# Motor_Driver_MK1.net
KiCad netlist of a schematic drawn in EAGLE
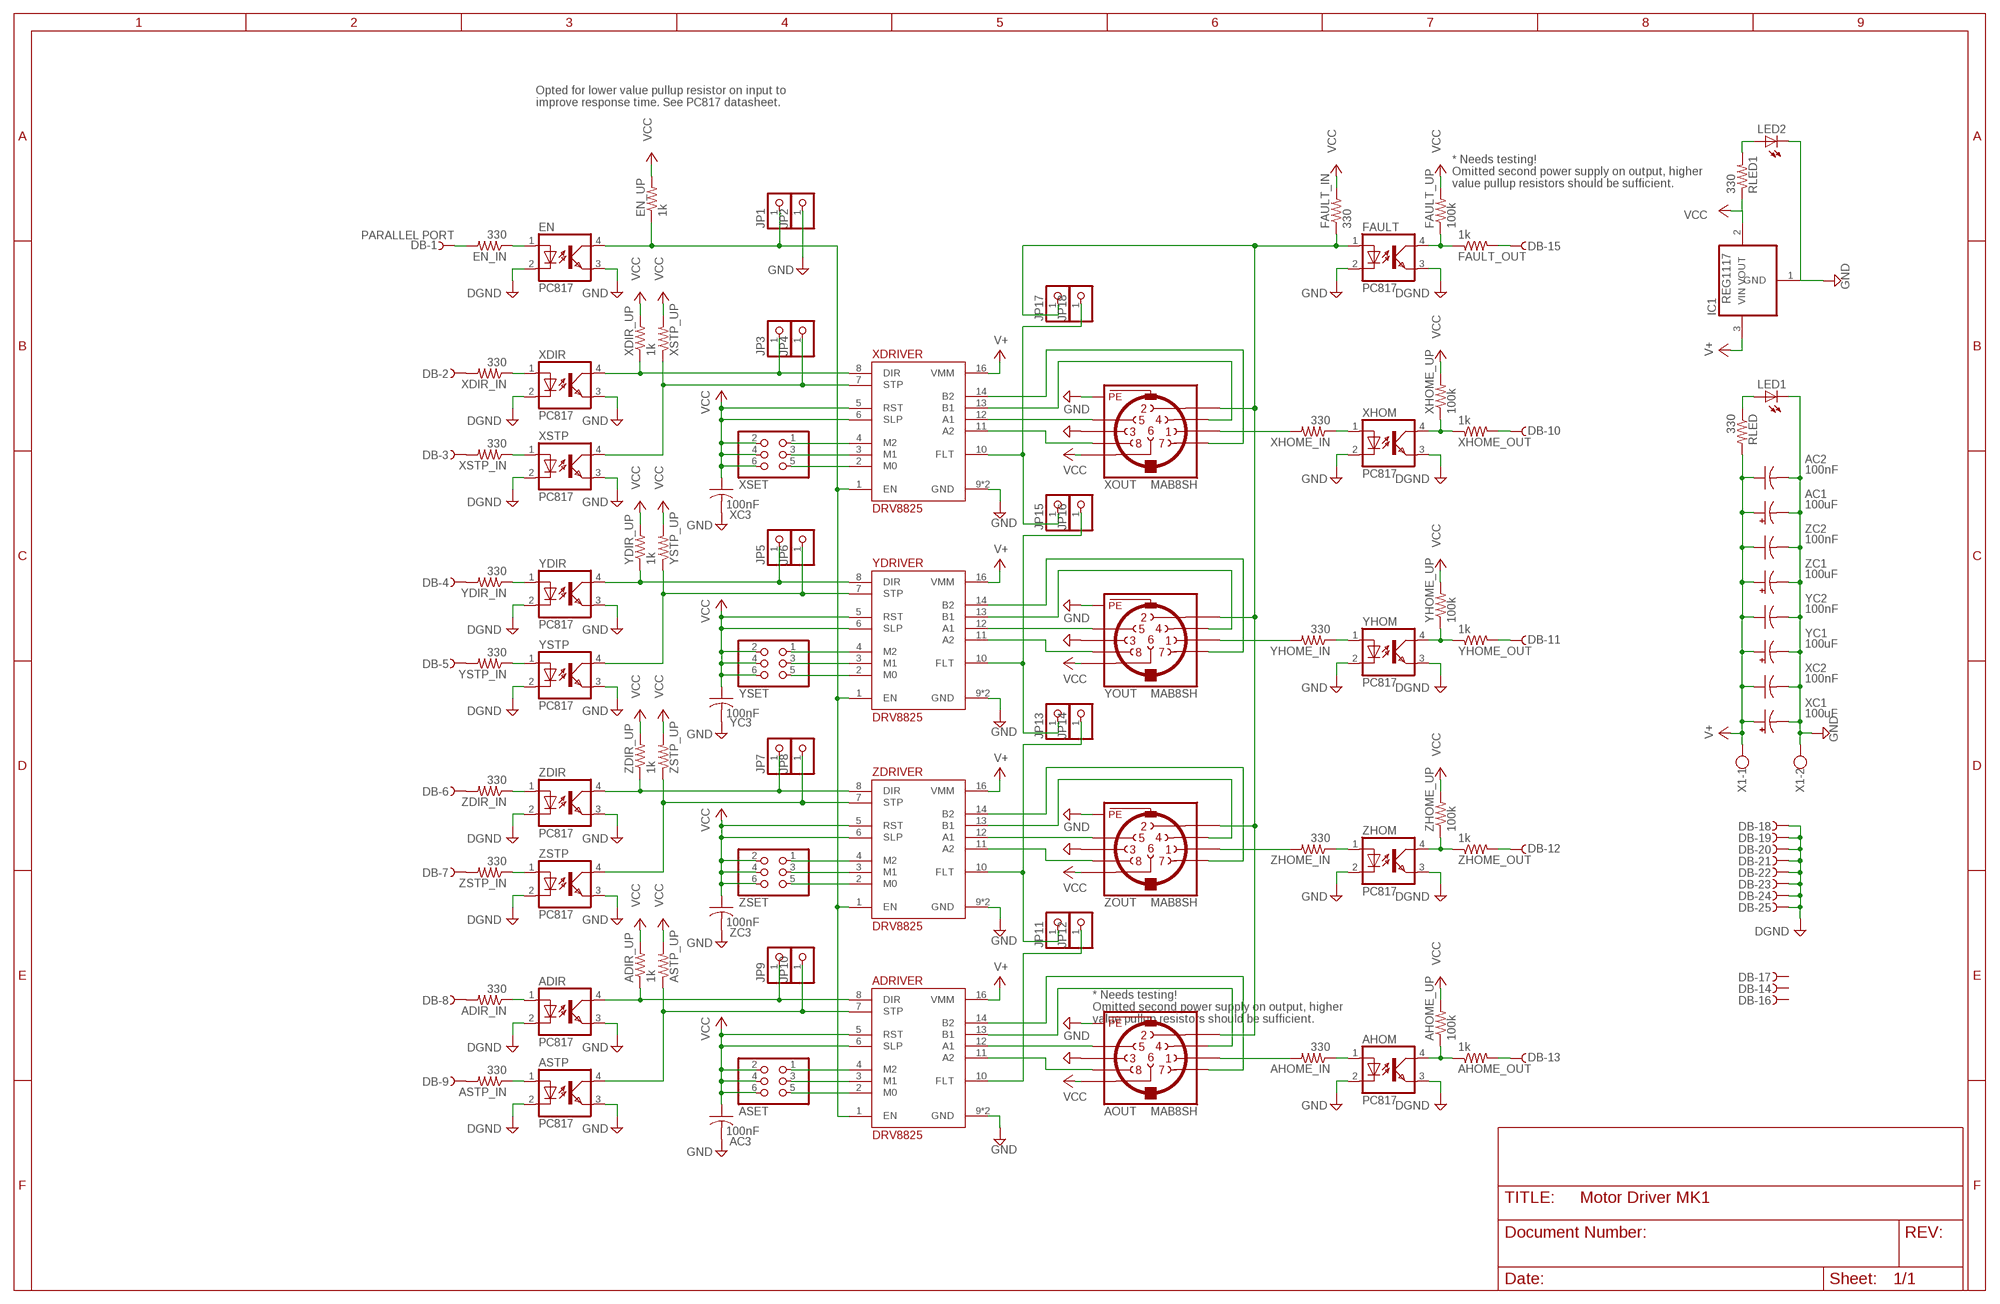
[diagram p0: schematic, sheet 1]

(export (version "E")
  (design (tool "Eeschema 10.0.6"))
  (components
    (comp (ref "AC1")
      (value "100uF")
      (footprint "eagle-import:SANYO-OSCON_SMD_E7")
      (libsource (lib "eagle-import") (part "CPOL-USSANYO_SMD_E7"))
    )
    (comp (ref "AC2")
      (value "100nF")
      (footprint "eagle-import:C0805")
      (libsource (lib "eagle-import") (part "C-USC0805"))
    )
    (comp (ref "AC3")
      (value "100nF")
      (footprint "eagle-import:C0805")
      (libsource (lib "eagle-import") (part "C-USC0805"))
    )
    (comp (ref "ADIR")
      (value "PC817")
      (footprint "eagle-import:DIL04")
      (fields (field (name "MPN") "PC817X4J000F"))
      (libsource (lib "eagle-import") (part "PC817"))
    )
    (comp (ref "ADIR_IN")
      (value "330")
      (footprint "eagle-import:R0805")
      (libsource (lib "eagle-import") (part "R-US_R0805"))
    )
    (comp (ref "ADIR_UP")
      (value "1k")
      (footprint "eagle-import:R0805")
      (libsource (lib "eagle-import") (part "R-US_R0805"))
    )
    (comp (ref "ADRIVER")
      (value "DRV8825")
      (footprint "eagle-import:DIP16")
      (libsource (lib "eagle-import") (part "DRV8825"))
    )
    (comp (ref "AHOM")
      (value "PC817")
      (footprint "eagle-import:DIL04")
      (fields (field (name "MPN") "PC817X4J000F"))
      (libsource (lib "eagle-import") (part "PC817"))
    )
    (comp (ref "AHOME_IN")
      (value "330")
      (footprint "eagle-import:R0805")
      (libsource (lib "eagle-import") (part "R-US_R0805"))
    )
    (comp (ref "AHOME_OUT")
      (value "1k")
      (footprint "eagle-import:R0805")
      (libsource (lib "eagle-import") (part "R-US_R0805"))
    )
    (comp (ref "AHOME_UP")
      (value "100k")
      (footprint "eagle-import:R0805")
      (libsource (lib "eagle-import") (part "R-US_R0805"))
    )
    (comp (ref "AOUT")
      (value "MAB8SH")
      (footprint "eagle-import:MAB8SH")
      (fields (field (name "MF") "FARNELL") (field (name "MPN") "MAB 8 SH"))
      (libsource (lib "eagle-import") (part "MAB8SH"))
    )
    (comp (ref "ASET")
      (value "PINHD-2X3")
      (footprint "eagle-import:2X03")
      (libsource (lib "eagle-import") (part "PINHD-2X3"))
    )
    (comp (ref "ASTP")
      (value "PC817")
      (footprint "eagle-import:DIL04")
      (fields (field (name "MPN") "PC817X4J000F"))
      (libsource (lib "eagle-import") (part "PC817"))
    )
    (comp (ref "ASTP_IN")
      (value "330")
      (footprint "eagle-import:R0805")
      (libsource (lib "eagle-import") (part "R-US_R0805"))
    )
    (comp (ref "ASTP_UP")
      (value "R-US_R0805")
      (footprint "eagle-import:R0805")
      (libsource (lib "eagle-import") (part "R-US_R0805"))
    )
    (comp (ref "DB")
      (value "PARALLEL PORT")
      (footprint "eagle-import:H2R25ST")
      (fields (field (name "MF") "TYCO ELECTRONICS") (field (name "MPN") "H2R25ST29J"))
      (libsource (lib "eagle-import") (part "D-SUB25-H2R25ST"))
    )
    (comp (ref "EN")
      (value "PC817")
      (footprint "eagle-import:DIL04")
      (fields (field (name "MPN") "PC817X4J000F"))
      (libsource (lib "eagle-import") (part "PC817"))
    )
    (comp (ref "EN_IN")
      (value "330")
      (footprint "eagle-import:R0805")
      (libsource (lib "eagle-import") (part "R-US_R0805"))
    )
    (comp (ref "EN_UP")
      (value "1k")
      (footprint "eagle-import:R0805")
      (libsource (lib "eagle-import") (part "R-US_R0805"))
    )
    (comp (ref "FAULT")
      (value "PC817")
      (footprint "eagle-import:DIL04")
      (fields (field (name "MPN") "PC817X4J000F"))
      (libsource (lib "eagle-import") (part "PC817"))
    )
    (comp (ref "FAULT_IN")
      (value "330")
      (footprint "eagle-import:R0805")
      (libsource (lib "eagle-import") (part "R-US_R0805"))
    )
    (comp (ref "FAULT_OUT")
      (value "1k")
      (footprint "eagle-import:R0805")
      (libsource (lib "eagle-import") (part "R-US_R0805"))
    )
    (comp (ref "FAULT_UP")
      (value "100k")
      (footprint "eagle-import:R0805")
      (libsource (lib "eagle-import") (part "R-US_R0805"))
    )
    (comp (ref "IC1")
      (value "REG1117")
      (footprint "eagle-import:SOT223")
      (libsource (lib "eagle-import") (part "REG1117"))
    )
    (comp (ref "JP1")
      (value "PINHD-1X1")
      (footprint "eagle-import:1X01")
      (libsource (lib "eagle-import") (part "PINHD-1X1"))
    )
    (comp (ref "JP2")
      (value "PINHD-1X1")
      (footprint "eagle-import:1X01")
      (libsource (lib "eagle-import") (part "PINHD-1X1"))
    )
    (comp (ref "JP3")
      (value "PINHD-1X1")
      (footprint "eagle-import:1X01")
      (libsource (lib "eagle-import") (part "PINHD-1X1"))
    )
    (comp (ref "JP4")
      (value "PINHD-1X1")
      (footprint "eagle-import:1X01")
      (libsource (lib "eagle-import") (part "PINHD-1X1"))
    )
    (comp (ref "JP5")
      (value "PINHD-1X1")
      (footprint "eagle-import:1X01")
      (libsource (lib "eagle-import") (part "PINHD-1X1"))
    )
    (comp (ref "JP6")
      (value "PINHD-1X1")
      (footprint "eagle-import:1X01")
      (libsource (lib "eagle-import") (part "PINHD-1X1"))
    )
    (comp (ref "JP7")
      (value "PINHD-1X1")
      (footprint "eagle-import:1X01")
      (libsource (lib "eagle-import") (part "PINHD-1X1"))
    )
    (comp (ref "JP8")
      (value "PINHD-1X1")
      (footprint "eagle-import:1X01")
      (libsource (lib "eagle-import") (part "PINHD-1X1"))
    )
    (comp (ref "JP9")
      (value "PINHD-1X1")
      (footprint "eagle-import:1X01")
      (libsource (lib "eagle-import") (part "PINHD-1X1"))
    )
    (comp (ref "JP10")
      (value "PINHD-1X1")
      (footprint "eagle-import:1X01")
      (libsource (lib "eagle-import") (part "PINHD-1X1"))
    )
    (comp (ref "JP11")
      (value "PINHD-1X1")
      (footprint "eagle-import:1X01")
      (libsource (lib "eagle-import") (part "PINHD-1X1"))
    )
    (comp (ref "JP12")
      (value "PINHD-1X1")
      (footprint "eagle-import:1X01")
      (libsource (lib "eagle-import") (part "PINHD-1X1"))
    )
    (comp (ref "JP13")
      (value "PINHD-1X1")
      (footprint "eagle-import:1X01")
      (libsource (lib "eagle-import") (part "PINHD-1X1"))
    )
    (comp (ref "JP14")
      (value "PINHD-1X1")
      (footprint "eagle-import:1X01")
      (libsource (lib "eagle-import") (part "PINHD-1X1"))
    )
    (comp (ref "JP15")
      (value "PINHD-1X1")
      (footprint "eagle-import:1X01")
      (libsource (lib "eagle-import") (part "PINHD-1X1"))
    )
    (comp (ref "JP16")
      (value "PINHD-1X1")
      (footprint "eagle-import:1X01")
      (libsource (lib "eagle-import") (part "PINHD-1X1"))
    )
    (comp (ref "JP17")
      (value "PINHD-1X1")
      (footprint "eagle-import:1X01")
      (libsource (lib "eagle-import") (part "PINHD-1X1"))
    )
    (comp (ref "JP18")
      (value "PINHD-1X1")
      (footprint "eagle-import:1X01")
      (libsource (lib "eagle-import") (part "PINHD-1X1"))
    )
    (comp (ref "LED1")
      (value "LEDCHIP-LED0805")
      (footprint "eagle-import:CHIP-LED0805")
      (libsource (lib "eagle-import") (part "LEDCHIP-LED0805"))
    )
    (comp (ref "LED2")
      (value "LEDCHIP-LED0805")
      (footprint "eagle-import:CHIP-LED0805")
      (libsource (lib "eagle-import") (part "LEDCHIP-LED0805"))
    )
    (comp (ref "RLED")
      (value "330")
      (footprint "eagle-import:R0805")
      (libsource (lib "eagle-import") (part "R-US_R0805"))
    )
    (comp (ref "RLED1")
      (value "330")
      (footprint "eagle-import:R0805")
      (libsource (lib "eagle-import") (part "R-US_R0805"))
    )
    (comp (ref "X1")
      (value "W237-102")
      (footprint "eagle-import:W237-102")
      (fields (field (name "MPN") "237-102"))
      (libsource (lib "eagle-import") (part "W237-102"))
    )
    (comp (ref "XC1")
      (value "100uF")
      (footprint "eagle-import:SANYO-OSCON_SMD_E7")
      (libsource (lib "eagle-import") (part "CPOL-USSANYO_SMD_E7"))
    )
    (comp (ref "XC2")
      (value "100nF")
      (footprint "eagle-import:C0805")
      (libsource (lib "eagle-import") (part "C-USC0805"))
    )
    (comp (ref "XC3")
      (value "100nF")
      (footprint "eagle-import:C0805")
      (libsource (lib "eagle-import") (part "C-USC0805"))
    )
    (comp (ref "XDIR")
      (value "PC817")
      (footprint "eagle-import:DIL04")
      (fields (field (name "MPN") "PC817X4J000F"))
      (libsource (lib "eagle-import") (part "PC817"))
    )
    (comp (ref "XDIR_IN")
      (value "330")
      (footprint "eagle-import:R0805")
      (libsource (lib "eagle-import") (part "R-US_R0805"))
    )
    (comp (ref "XDIR_UP")
      (value "1k")
      (footprint "eagle-import:R0805")
      (libsource (lib "eagle-import") (part "R-US_R0805"))
    )
    (comp (ref "XDRIVER")
      (value "DRV8825")
      (footprint "eagle-import:DIP16")
      (libsource (lib "eagle-import") (part "DRV8825"))
    )
    (comp (ref "XHOM")
      (value "PC817")
      (footprint "eagle-import:DIL04")
      (fields (field (name "MPN") "PC817X4J000F"))
      (libsource (lib "eagle-import") (part "PC817"))
    )
    (comp (ref "XHOME_IN")
      (value "330")
      (footprint "eagle-import:R0805")
      (libsource (lib "eagle-import") (part "R-US_R0805"))
    )
    (comp (ref "XHOME_OUT")
      (value "1k")
      (footprint "eagle-import:R0805")
      (libsource (lib "eagle-import") (part "R-US_R0805"))
    )
    (comp (ref "XHOME_UP")
      (value "100k")
      (footprint "eagle-import:R0805")
      (libsource (lib "eagle-import") (part "R-US_R0805"))
    )
    (comp (ref "XOUT")
      (value "MAB8SH")
      (footprint "eagle-import:MAB8SH")
      (fields (field (name "MF") "FARNELL") (field (name "MPN") "MAB 8 SH"))
      (libsource (lib "eagle-import") (part "MAB8SH"))
    )
    (comp (ref "XSET")
      (value "PINHD-2X3")
      (footprint "eagle-import:2X03")
      (libsource (lib "eagle-import") (part "PINHD-2X3"))
    )
    (comp (ref "XSTP")
      (value "PC817")
      (footprint "eagle-import:DIL04")
      (fields (field (name "MPN") "PC817X4J000F"))
      (libsource (lib "eagle-import") (part "PC817"))
    )
    (comp (ref "XSTP_IN")
      (value "330")
      (footprint "eagle-import:R0805")
      (libsource (lib "eagle-import") (part "R-US_R0805"))
    )
    (comp (ref "XSTP_UP")
      (value "R-US_R0805")
      (footprint "eagle-import:R0805")
      (libsource (lib "eagle-import") (part "R-US_R0805"))
    )
    (comp (ref "YC1")
      (value "100uF")
      (footprint "eagle-import:SANYO-OSCON_SMD_E7")
      (libsource (lib "eagle-import") (part "CPOL-USSANYO_SMD_E7"))
    )
    (comp (ref "YC2")
      (value "100nF")
      (footprint "eagle-import:C0805")
      (libsource (lib "eagle-import") (part "C-USC0805"))
    )
    (comp (ref "YC3")
      (value "100nF")
      (footprint "eagle-import:C0805")
      (libsource (lib "eagle-import") (part "C-USC0805"))
    )
    (comp (ref "YDIR")
      (value "PC817")
      (footprint "eagle-import:DIL04")
      (fields (field (name "MPN") "PC817X4J000F"))
      (libsource (lib "eagle-import") (part "PC817"))
    )
    (comp (ref "YDIR_IN")
      (value "330")
      (footprint "eagle-import:R0805")
      (libsource (lib "eagle-import") (part "R-US_R0805"))
    )
    (comp (ref "YDIR_UP")
      (value "1k")
      (footprint "eagle-import:R0805")
      (libsource (lib "eagle-import") (part "R-US_R0805"))
    )
    (comp (ref "YDRIVER")
      (value "DRV8825")
      (footprint "eagle-import:DIP16")
      (libsource (lib "eagle-import") (part "DRV8825"))
    )
    (comp (ref "YHOM")
      (value "PC817")
      (footprint "eagle-import:DIL04")
      (fields (field (name "MPN") "PC817X4J000F"))
      (libsource (lib "eagle-import") (part "PC817"))
    )
    (comp (ref "YHOME_IN")
      (value "330")
      (footprint "eagle-import:R0805")
      (libsource (lib "eagle-import") (part "R-US_R0805"))
    )
    (comp (ref "YHOME_OUT")
      (value "1k")
      (footprint "eagle-import:R0805")
      (libsource (lib "eagle-import") (part "R-US_R0805"))
    )
    (comp (ref "YHOME_UP")
      (value "100k")
      (footprint "eagle-import:R0805")
      (libsource (lib "eagle-import") (part "R-US_R0805"))
    )
    (comp (ref "YOUT")
      (value "MAB8SH")
      (footprint "eagle-import:MAB8SH")
      (fields (field (name "MF") "FARNELL") (field (name "MPN") "MAB 8 SH"))
      (libsource (lib "eagle-import") (part "MAB8SH"))
    )
    (comp (ref "YSET")
      (value "PINHD-2X3")
      (footprint "eagle-import:2X03")
      (libsource (lib "eagle-import") (part "PINHD-2X3"))
    )
    (comp (ref "YSTP")
      (value "PC817")
      (footprint "eagle-import:DIL04")
      (fields (field (name "MPN") "PC817X4J000F"))
      (libsource (lib "eagle-import") (part "PC817"))
    )
    (comp (ref "YSTP_IN")
      (value "330")
      (footprint "eagle-import:R0805")
      (libsource (lib "eagle-import") (part "R-US_R0805"))
    )
    (comp (ref "YSTP_UP")
      (value "R-US_R0805")
      (footprint "eagle-import:R0805")
      (libsource (lib "eagle-import") (part "R-US_R0805"))
    )
    (comp (ref "ZC1")
      (value "100uF")
      (footprint "eagle-import:SANYO-OSCON_SMD_E7")
      (libsource (lib "eagle-import") (part "CPOL-USSANYO_SMD_E7"))
    )
    (comp (ref "ZC2")
      (value "100nF")
      (footprint "eagle-import:C0805")
      (libsource (lib "eagle-import") (part "C-USC0805"))
    )
    (comp (ref "ZC3")
      (value "100nF")
      (footprint "eagle-import:C0805")
      (libsource (lib "eagle-import") (part "C-USC0805"))
    )
    (comp (ref "ZDIR")
      (value "PC817")
      (footprint "eagle-import:DIL04")
      (fields (field (name "MPN") "PC817X4J000F"))
      (libsource (lib "eagle-import") (part "PC817"))
    )
    (comp (ref "ZDIR_IN")
      (value "330")
      (footprint "eagle-import:R0805")
      (libsource (lib "eagle-import") (part "R-US_R0805"))
    )
    (comp (ref "ZDIR_UP")
      (value "1k")
      (footprint "eagle-import:R0805")
      (libsource (lib "eagle-import") (part "R-US_R0805"))
    )
    (comp (ref "ZDRIVER")
      (value "DRV8825")
      (footprint "eagle-import:DIP16")
      (libsource (lib "eagle-import") (part "DRV8825"))
    )
    (comp (ref "ZHOM")
      (value "PC817")
      (footprint "eagle-import:DIL04")
      (fields (field (name "MPN") "PC817X4J000F"))
      (libsource (lib "eagle-import") (part "PC817"))
    )
    (comp (ref "ZHOME_IN")
      (value "330")
      (footprint "eagle-import:R0805")
      (libsource (lib "eagle-import") (part "R-US_R0805"))
    )
    (comp (ref "ZHOME_OUT")
      (value "1k")
      (footprint "eagle-import:R0805")
      (libsource (lib "eagle-import") (part "R-US_R0805"))
    )
    (comp (ref "ZHOME_UP")
      (value "100k")
      (footprint "eagle-import:R0805")
      (libsource (lib "eagle-import") (part "R-US_R0805"))
    )
    (comp (ref "ZOUT")
      (value "MAB8SH")
      (footprint "eagle-import:MAB8SH")
      (fields (field (name "MF") "FARNELL") (field (name "MPN") "MAB 8 SH"))
      (libsource (lib "eagle-import") (part "MAB8SH"))
    )
    (comp (ref "ZSET")
      (value "PINHD-2X3")
      (footprint "eagle-import:2X03")
      (libsource (lib "eagle-import") (part "PINHD-2X3"))
    )
    (comp (ref "ZSTP")
      (value "PC817")
      (footprint "eagle-import:DIL04")
      (fields (field (name "MPN") "PC817X4J000F"))
      (libsource (lib "eagle-import") (part "PC817"))
    )
    (comp (ref "ZSTP_IN")
      (value "330")
      (footprint "eagle-import:R0805")
      (libsource (lib "eagle-import") (part "R-US_R0805"))
    )
    (comp (ref "ZSTP_UP")
      (value "R-US_R0805")
      (footprint "eagle-import:R0805")
      (libsource (lib "eagle-import") (part "R-US_R0805"))
    )
  )
  (nets
    (net (code "1") (name "DGND") (class "Default")
      (node (ref "ADIR") (pin "2") (pinfunction "C_2") (pintype "passive"))
      (node (ref "AHOM") (pin "3") (pinfunction "EMIT_3") (pintype "passive"))
      (node (ref "ASTP") (pin "2") (pinfunction "C_2") (pintype "passive"))
      (node (ref "DB") (pin "18") (pinfunction "F_18") (pintype "passive"))
      (node (ref "DB") (pin "19") (pinfunction "F_19") (pintype "passive"))
      (node (ref "DB") (pin "20") (pinfunction "F_20") (pintype "passive"))
      (node (ref "DB") (pin "21") (pinfunction "F_21") (pintype "passive"))
      (node (ref "DB") (pin "22") (pinfunction "F_22") (pintype "passive"))
      (node (ref "DB") (pin "23") (pinfunction "F_23") (pintype "passive"))
      (node (ref "DB") (pin "24") (pinfunction "F_24") (pintype "passive"))
      (node (ref "DB") (pin "25") (pinfunction "F_25") (pintype "passive"))
      (node (ref "EN") (pin "2") (pinfunction "C_2") (pintype "passive"))
      (node (ref "FAULT") (pin "3") (pinfunction "EMIT_3") (pintype "passive"))
      (node (ref "XDIR") (pin "2") (pinfunction "C_2") (pintype "passive"))
      (node (ref "XHOM") (pin "3") (pinfunction "EMIT_3") (pintype "passive"))
      (node (ref "XSTP") (pin "2") (pinfunction "C_2") (pintype "passive"))
      (node (ref "YDIR") (pin "2") (pinfunction "C_2") (pintype "passive"))
      (node (ref "YHOM") (pin "3") (pinfunction "EMIT_3") (pintype "passive"))
      (node (ref "YSTP") (pin "2") (pinfunction "C_2") (pintype "passive"))
      (node (ref "ZDIR") (pin "2") (pinfunction "C_2") (pintype "passive"))
      (node (ref "ZHOM") (pin "3") (pinfunction "EMIT_3") (pintype "passive"))
      (node (ref "ZSTP") (pin "2") (pinfunction "C_2") (pintype "passive"))
    )
    (net (code "2") (name "GND") (class "Default")
      (node (ref "AC1") (pin "-") (pinfunction "-_-") (pintype "passive"))
      (node (ref "AC2") (pin "2") (pinfunction "2_2") (pintype "passive"))
      (node (ref "AC3") (pin "2") (pinfunction "2_2") (pintype "passive"))
      (node (ref "ADIR") (pin "3") (pinfunction "EMIT_3") (pintype "passive"))
      (node (ref "ADRIVER") (pin "15") (pinfunction "GND_15") (pintype "bidirectional"))
      (node (ref "ADRIVER") (pin "9") (pinfunction "GND_9") (pintype "bidirectional"))
      (node (ref "AHOM") (pin "2") (pinfunction "C_2") (pintype "passive"))
      (node (ref "AOUT") (pin "3") (pinfunction "3_3") (pintype "passive"))
      (node (ref "AOUT") (pin "PE") (pinfunction "PE_PE") (pintype "power_in"))
      (node (ref "AOUT") (pin "PE@") (pinfunction "PE_PE@") (pintype "power_in"))
      (node (ref "ASTP") (pin "3") (pinfunction "EMIT_3") (pintype "passive"))
      (node (ref "EN") (pin "3") (pinfunction "EMIT_3") (pintype "passive"))
      (node (ref "FAULT") (pin "2") (pinfunction "C_2") (pintype "passive"))
      (node (ref "IC1") (pin "1") (pinfunction "GND_1") (pintype "power_in"))
      (node (ref "JP2") (pin "1") (pinfunction "1_1") (pintype "passive"))
      (node (ref "LED1") (pin "C") (pinfunction "C_C") (pintype "passive"))
      (node (ref "LED2") (pin "C") (pinfunction "C_C") (pintype "passive"))
      (node (ref "X1") (pin "2") (pinfunction "KL_2") (pintype "passive"))
      (node (ref "XC1") (pin "-") (pinfunction "-_-") (pintype "passive"))
      (node (ref "XC2") (pin "2") (pinfunction "2_2") (pintype "passive"))
      (node (ref "XC3") (pin "2") (pinfunction "2_2") (pintype "passive"))
      (node (ref "XDIR") (pin "3") (pinfunction "EMIT_3") (pintype "passive"))
      (node (ref "XDRIVER") (pin "15") (pinfunction "GND_15") (pintype "bidirectional"))
      (node (ref "XDRIVER") (pin "9") (pinfunction "GND_9") (pintype "bidirectional"))
      (node (ref "XHOM") (pin "2") (pinfunction "C_2") (pintype "passive"))
      (node (ref "XOUT") (pin "3") (pinfunction "3_3") (pintype "passive"))
      (node (ref "XOUT") (pin "PE") (pinfunction "PE_PE") (pintype "power_in"))
      (node (ref "XOUT") (pin "PE@") (pinfunction "PE_PE@") (pintype "power_in"))
      (node (ref "XSTP") (pin "3") (pinfunction "EMIT_3") (pintype "passive"))
      (node (ref "YC1") (pin "-") (pinfunction "-_-") (pintype "passive"))
      (node (ref "YC2") (pin "2") (pinfunction "2_2") (pintype "passive"))
      (node (ref "YC3") (pin "2") (pinfunction "2_2") (pintype "passive"))
      (node (ref "YDIR") (pin "3") (pinfunction "EMIT_3") (pintype "passive"))
      (node (ref "YDRIVER") (pin "15") (pinfunction "GND_15") (pintype "bidirectional"))
      (node (ref "YDRIVER") (pin "9") (pinfunction "GND_9") (pintype "bidirectional"))
      (node (ref "YHOM") (pin "2") (pinfunction "C_2") (pintype "passive"))
      (node (ref "YOUT") (pin "3") (pinfunction "3_3") (pintype "passive"))
      (node (ref "YOUT") (pin "PE") (pinfunction "PE_PE") (pintype "power_in"))
      (node (ref "YOUT") (pin "PE@") (pinfunction "PE_PE@") (pintype "power_in"))
      (node (ref "YSTP") (pin "3") (pinfunction "EMIT_3") (pintype "passive"))
      (node (ref "ZC1") (pin "-") (pinfunction "-_-") (pintype "passive"))
      (node (ref "ZC2") (pin "2") (pinfunction "2_2") (pintype "passive"))
      (node (ref "ZC3") (pin "2") (pinfunction "2_2") (pintype "passive"))
      (node (ref "ZDIR") (pin "3") (pinfunction "EMIT_3") (pintype "passive"))
      (node (ref "ZDRIVER") (pin "15") (pinfunction "GND_15") (pintype "bidirectional"))
      (node (ref "ZDRIVER") (pin "9") (pinfunction "GND_9") (pintype "bidirectional"))
      (node (ref "ZHOM") (pin "2") (pinfunction "C_2") (pintype "passive"))
      (node (ref "ZOUT") (pin "3") (pinfunction "3_3") (pintype "passive"))
      (node (ref "ZOUT") (pin "PE") (pinfunction "PE_PE") (pintype "power_in"))
      (node (ref "ZOUT") (pin "PE@") (pinfunction "PE_PE@") (pintype "power_in"))
      (node (ref "ZSTP") (pin "3") (pinfunction "EMIT_3") (pintype "passive"))
    )
    (net (code "3") (name "Net-(ADIR-A)") (class "Default")
      (node (ref "ADIR") (pin "1") (pinfunction "A_1") (pintype "passive"))
      (node (ref "ADIR_IN") (pin "1") (pinfunction "1_1") (pintype "passive"))
    )
    (net (code "4") (name "Net-(ADIR-COL)") (class "Default")
      (node (ref "ADIR") (pin "4") (pinfunction "COL_4") (pintype "passive"))
      (node (ref "ADIR_UP") (pin "1") (pinfunction "1_1") (pintype "passive"))
      (node (ref "ADRIVER") (pin "8") (pinfunction "DIR_8") (pintype "bidirectional"))
      (node (ref "JP9") (pin "1") (pinfunction "1_1") (pintype "passive"))
    )
    (net (code "5") (name "Net-(ADRIVER-A1)") (class "Default")
      (node (ref "ADRIVER") (pin "12") (pinfunction "A1_12") (pintype "bidirectional"))
      (node (ref "AOUT") (pin "5") (pinfunction "5_5") (pintype "passive"))
    )
    (net (code "6") (name "Net-(ADRIVER-A2)") (class "Default")
      (node (ref "ADRIVER") (pin "11") (pinfunction "A2_11") (pintype "bidirectional"))
      (node (ref "AOUT") (pin "8") (pinfunction "8_8") (pintype "passive"))
    )
    (net (code "7") (name "Net-(ADRIVER-B1)") (class "Default")
      (node (ref "ADRIVER") (pin "13") (pinfunction "B1_13") (pintype "bidirectional"))
      (node (ref "AOUT") (pin "4") (pinfunction "4_4") (pintype "passive"))
    )
    (net (code "8") (name "Net-(ADRIVER-B2)") (class "Default")
      (node (ref "ADRIVER") (pin "14") (pinfunction "B2_14") (pintype "bidirectional"))
      (node (ref "AOUT") (pin "7") (pinfunction "7_7") (pintype "passive"))
    )
    (net (code "9") (name "Net-(ADRIVER-EN)") (class "Default")
      (node (ref "ADRIVER") (pin "1") (pinfunction "EN_1") (pintype "bidirectional"))
      (node (ref "EN") (pin "4") (pinfunction "COL_4") (pintype "passive"))
      (node (ref "EN_UP") (pin "1") (pinfunction "1_1") (pintype "passive"))
      (node (ref "JP1") (pin "1") (pinfunction "1_1") (pintype "passive"))
      (node (ref "XDRIVER") (pin "1") (pinfunction "EN_1") (pintype "bidirectional"))
      (node (ref "YDRIVER") (pin "1") (pinfunction "EN_1") (pintype "bidirectional"))
      (node (ref "ZDRIVER") (pin "1") (pinfunction "EN_1") (pintype "bidirectional"))
    )
    (net (code "10") (name "Net-(ADRIVER-FLT)") (class "Default")
      (node (ref "ADRIVER") (pin "10") (pinfunction "FLT_10") (pintype "bidirectional"))
      (node (ref "JP12") (pin "1") (pinfunction "1_1") (pintype "passive"))
    )
    (net (code "11") (name "Net-(ADRIVER-M0)") (class "Default")
      (node (ref "ADRIVER") (pin "2") (pinfunction "M0_2") (pintype "bidirectional"))
      (node (ref "ASET") (pin "5") (pinfunction "5_5") (pintype "passive"))
    )
    (net (code "12") (name "Net-(ADRIVER-M1)") (class "Default")
      (node (ref "ADRIVER") (pin "3") (pinfunction "M1_3") (pintype "bidirectional"))
      (node (ref "ASET") (pin "3") (pinfunction "3_3") (pintype "passive"))
    )
    (net (code "13") (name "Net-(ADRIVER-M2)") (class "Default")
      (node (ref "ADRIVER") (pin "4") (pinfunction "M2_4") (pintype "bidirectional"))
      (node (ref "ASET") (pin "1") (pinfunction "1_1") (pintype "passive"))
    )
    (net (code "14") (name "Net-(ADRIVER-STP)") (class "Default")
      (node (ref "ADRIVER") (pin "7") (pinfunction "STP_7") (pintype "bidirectional"))
      (node (ref "ASTP") (pin "4") (pinfunction "COL_4") (pintype "passive"))
      (node (ref "ASTP_UP") (pin "1") (pinfunction "1_1") (pintype "passive"))
      (node (ref "JP10") (pin "1") (pinfunction "1_1") (pintype "passive"))
    )
    (net (code "15") (name "Net-(AHOM-A)") (class "Default")
      (node (ref "AHOM") (pin "1") (pinfunction "A_1") (pintype "passive"))
      (node (ref "AHOME_IN") (pin "1") (pinfunction "1_1") (pintype "passive"))
    )
    (net (code "16") (name "Net-(AHOM-COL)") (class "Default")
      (node (ref "AHOM") (pin "4") (pinfunction "COL_4") (pintype "passive"))
      (node (ref "AHOME_OUT") (pin "1") (pinfunction "1_1") (pintype "passive"))
      (node (ref "AHOME_UP") (pin "1") (pinfunction "1_1") (pintype "passive"))
    )
    (net (code "17") (name "Net-(AHOME_IN-Pad2)") (class "Default")
      (node (ref "AHOME_IN") (pin "2") (pinfunction "2_2") (pintype "passive"))
      (node (ref "AOUT") (pin "1") (pinfunction "1_1") (pintype "passive"))
    )
    (net (code "18") (name "Net-(ASTP-A)") (class "Default")
      (node (ref "ASTP") (pin "1") (pinfunction "A_1") (pintype "passive"))
      (node (ref "ASTP_IN") (pin "1") (pinfunction "1_1") (pintype "passive"))
    )
    (net (code "19") (name "Net-(DBA-F)") (class "Default")
      (node (ref "DB") (pin "1") (pinfunction "F_1") (pintype "passive"))
      (node (ref "EN_IN") (pin "2") (pinfunction "2_2") (pintype "passive"))
    )
    (net (code "20") (name "Net-(DBB-F)") (class "Default")
      (node (ref "DB") (pin "10") (pinfunction "F_10") (pintype "passive"))
      (node (ref "XHOME_OUT") (pin "2") (pinfunction "2_2") (pintype "passive"))
    )
    (net (code "21") (name "Net-(DBC-F)") (class "Default")
      (node (ref "DB") (pin "11") (pinfunction "F_11") (pintype "passive"))
      (node (ref "YHOME_OUT") (pin "2") (pinfunction "2_2") (pintype "passive"))
    )
    (net (code "22") (name "Net-(DBD-F)") (class "Default")
      (node (ref "DB") (pin "12") (pinfunction "F_12") (pintype "passive"))
      (node (ref "ZHOME_OUT") (pin "2") (pinfunction "2_2") (pintype "passive"))
    )
    (net (code "23") (name "Net-(DBE-F)") (class "Default")
      (node (ref "AHOME_OUT") (pin "2") (pinfunction "2_2") (pintype "passive"))
      (node (ref "DB") (pin "13") (pinfunction "F_13") (pintype "passive"))
    )
    (net (code "24") (name "Net-(DBG-F)") (class "Default")
      (node (ref "DB") (pin "15") (pinfunction "F_15") (pintype "passive"))
      (node (ref "FAULT_OUT") (pin "2") (pinfunction "2_2") (pintype "passive"))
    )
    (net (code "25") (name "Net-(DBL-F)") (class "Default")
      (node (ref "DB") (pin "2") (pinfunction "F_2") (pintype "passive"))
      (node (ref "XDIR_IN") (pin "2") (pinfunction "2_2") (pintype "passive"))
    )
    (net (code "26") (name "Net-(DBS-F)") (class "Default")
      (node (ref "DB") (pin "3") (pinfunction "F_3") (pintype "passive"))
      (node (ref "XSTP_IN") (pin "2") (pinfunction "2_2") (pintype "passive"))
    )
    (net (code "27") (name "Net-(DBT-F)") (class "Default")
      (node (ref "DB") (pin "4") (pinfunction "F_4") (pintype "passive"))
      (node (ref "YDIR_IN") (pin "2") (pinfunction "2_2") (pintype "passive"))
    )
    (net (code "28") (name "Net-(DBU-F)") (class "Default")
      (node (ref "DB") (pin "5") (pinfunction "F_5") (pintype "passive"))
      (node (ref "YSTP_IN") (pin "2") (pinfunction "2_2") (pintype "passive"))
    )
    (net (code "29") (name "Net-(DBV-F)") (class "Default")
      (node (ref "DB") (pin "6") (pinfunction "F_6") (pintype "passive"))
      (node (ref "ZDIR_IN") (pin "2") (pinfunction "2_2") (pintype "passive"))
    )
    (net (code "30") (name "Net-(DBW-F)") (class "Default")
      (node (ref "DB") (pin "7") (pinfunction "F_7") (pintype "passive"))
      (node (ref "ZSTP_IN") (pin "2") (pinfunction "2_2") (pintype "passive"))
    )
    (net (code "31") (name "Net-(DBX-F)") (class "Default")
      (node (ref "ADIR_IN") (pin "2") (pinfunction "2_2") (pintype "passive"))
      (node (ref "DB") (pin "8") (pinfunction "F_8") (pintype "passive"))
    )
    (net (code "32") (name "Net-(DBY-F)") (class "Default")
      (node (ref "ASTP_IN") (pin "2") (pinfunction "2_2") (pintype "passive"))
      (node (ref "DB") (pin "9") (pinfunction "F_9") (pintype "passive"))
    )
    (net (code "33") (name "Net-(EN-A)") (class "Default")
      (node (ref "EN") (pin "1") (pinfunction "A_1") (pintype "passive"))
      (node (ref "EN_IN") (pin "1") (pinfunction "1_1") (pintype "passive"))
    )
    (net (code "34") (name "Net-(FAULT-A)") (class "Default")
      (node (ref "AOUT") (pin "2") (pinfunction "2_2") (pintype "passive"))
      (node (ref "FAULT") (pin "1") (pinfunction "A_1") (pintype "passive"))
      (node (ref "FAULT_IN") (pin "1") (pinfunction "1_1") (pintype "passive"))
      (node (ref "JP17") (pin "1") (pinfunction "1_1") (pintype "passive"))
      (node (ref "XOUT") (pin "2") (pinfunction "2_2") (pintype "passive"))
      (node (ref "YOUT") (pin "2") (pinfunction "2_2") (pintype "passive"))
      (node (ref "ZOUT") (pin "2") (pinfunction "2_2") (pintype "passive"))
    )
    (net (code "35") (name "Net-(FAULT-COL)") (class "Default")
      (node (ref "FAULT") (pin "4") (pinfunction "COL_4") (pintype "passive"))
      (node (ref "FAULT_OUT") (pin "1") (pinfunction "1_1") (pintype "passive"))
      (node (ref "FAULT_UP") (pin "1") (pinfunction "1_1") (pintype "passive"))
    )
    (net (code "36") (name "Net-(LED1-PadA)") (class "Default")
      (node (ref "LED1") (pin "A") (pinfunction "A_A") (pintype "passive"))
      (node (ref "RLED") (pin "1") (pinfunction "1_1") (pintype "passive"))
    )
    (net (code "37") (name "Net-(LED2-PadA)") (class "Default")
      (node (ref "LED2") (pin "A") (pinfunction "A_A") (pintype "passive"))
      (node (ref "RLED1") (pin "2") (pinfunction "2_2") (pintype "passive"))
    )
    (net (code "38") (name "Net-(XDIR-A)") (class "Default")
      (node (ref "XDIR") (pin "1") (pinfunction "A_1") (pintype "passive"))
      (node (ref "XDIR_IN") (pin "1") (pinfunction "1_1") (pintype "passive"))
    )
    (net (code "39") (name "Net-(XDIR-COL)") (class "Default")
      (node (ref "JP3") (pin "1") (pinfunction "1_1") (pintype "passive"))
      (node (ref "XDIR") (pin "4") (pinfunction "COL_4") (pintype "passive"))
      (node (ref "XDIR_UP") (pin "1") (pinfunction "1_1") (pintype "passive"))
      (node (ref "XDRIVER") (pin "8") (pinfunction "DIR_8") (pintype "bidirectional"))
    )
    (net (code "40") (name "Net-(XDRIVER-A1)") (class "Default")
      (node (ref "XDRIVER") (pin "12") (pinfunction "A1_12") (pintype "bidirectional"))
      (node (ref "XOUT") (pin "5") (pinfunction "5_5") (pintype "passive"))
    )
    (net (code "41") (name "Net-(XDRIVER-A2)") (class "Default")
      (node (ref "XDRIVER") (pin "11") (pinfunction "A2_11") (pintype "bidirectional"))
      (node (ref "XOUT") (pin "8") (pinfunction "8_8") (pintype "passive"))
    )
    (net (code "42") (name "Net-(XDRIVER-B1)") (class "Default")
      (node (ref "XDRIVER") (pin "13") (pinfunction "B1_13") (pintype "bidirectional"))
      (node (ref "XOUT") (pin "4") (pinfunction "4_4") (pintype "passive"))
    )
    (net (code "43") (name "Net-(XDRIVER-B2)") (class "Default")
      (node (ref "XDRIVER") (pin "14") (pinfunction "B2_14") (pintype "bidirectional"))
      (node (ref "XOUT") (pin "7") (pinfunction "7_7") (pintype "passive"))
    )
    (net (code "44") (name "Net-(XDRIVER-FLT)") (class "Default")
      (node (ref "JP15") (pin "1") (pinfunction "1_1") (pintype "passive"))
      (node (ref "JP18") (pin "1") (pinfunction "1_1") (pintype "passive"))
      (node (ref "XDRIVER") (pin "10") (pinfunction "FLT_10") (pintype "bidirectional"))
    )
    (net (code "45") (name "Net-(XDRIVER-M0)") (class "Default")
      (node (ref "XDRIVER") (pin "2") (pinfunction "M0_2") (pintype "bidirectional"))
      (node (ref "XSET") (pin "5") (pinfunction "5_5") (pintype "passive"))
    )
    (net (code "46") (name "Net-(XDRIVER-M1)") (class "Default")
      (node (ref "XDRIVER") (pin "3") (pinfunction "M1_3") (pintype "bidirectional"))
      (node (ref "XSET") (pin "3") (pinfunction "3_3") (pintype "passive"))
    )
    (net (code "47") (name "Net-(XDRIVER-M2)") (class "Default")
      (node (ref "XDRIVER") (pin "4") (pinfunction "M2_4") (pintype "bidirectional"))
      (node (ref "XSET") (pin "1") (pinfunction "1_1") (pintype "passive"))
    )
    (net (code "48") (name "Net-(XDRIVER-STP)") (class "Default")
      (node (ref "JP4") (pin "1") (pinfunction "1_1") (pintype "passive"))
      (node (ref "XDRIVER") (pin "7") (pinfunction "STP_7") (pintype "bidirectional"))
      (node (ref "XSTP") (pin "4") (pinfunction "COL_4") (pintype "passive"))
      (node (ref "XSTP_UP") (pin "1") (pinfunction "1_1") (pintype "passive"))
    )
    (net (code "49") (name "Net-(XHOM-A)") (class "Default")
      (node (ref "XHOM") (pin "1") (pinfunction "A_1") (pintype "passive"))
      (node (ref "XHOME_IN") (pin "1") (pinfunction "1_1") (pintype "passive"))
    )
    (net (code "50") (name "Net-(XHOM-COL)") (class "Default")
      (node (ref "XHOM") (pin "4") (pinfunction "COL_4") (pintype "passive"))
      (node (ref "XHOME_OUT") (pin "1") (pinfunction "1_1") (pintype "passive"))
      (node (ref "XHOME_UP") (pin "1") (pinfunction "1_1") (pintype "passive"))
    )
    (net (code "51") (name "Net-(XHOME_IN-Pad2)") (class "Default")
      (node (ref "XHOME_IN") (pin "2") (pinfunction "2_2") (pintype "passive"))
      (node (ref "XOUT") (pin "1") (pinfunction "1_1") (pintype "passive"))
    )
    (net (code "52") (name "Net-(XSTP-A)") (class "Default")
      (node (ref "XSTP") (pin "1") (pinfunction "A_1") (pintype "passive"))
      (node (ref "XSTP_IN") (pin "1") (pinfunction "1_1") (pintype "passive"))
    )
    (net (code "53") (name "Net-(YDIR-A)") (class "Default")
      (node (ref "YDIR") (pin "1") (pinfunction "A_1") (pintype "passive"))
      (node (ref "YDIR_IN") (pin "1") (pinfunction "1_1") (pintype "passive"))
    )
    (net (code "54") (name "Net-(YDIR-COL)") (class "Default")
      (node (ref "JP5") (pin "1") (pinfunction "1_1") (pintype "passive"))
      (node (ref "YDIR") (pin "4") (pinfunction "COL_4") (pintype "passive"))
      (node (ref "YDIR_UP") (pin "1") (pinfunction "1_1") (pintype "passive"))
      (node (ref "YDRIVER") (pin "8") (pinfunction "DIR_8") (pintype "bidirectional"))
    )
    (net (code "55") (name "Net-(YDRIVER-A1)") (class "Default")
      (node (ref "YDRIVER") (pin "12") (pinfunction "A1_12") (pintype "bidirectional"))
      (node (ref "YOUT") (pin "5") (pinfunction "5_5") (pintype "passive"))
    )
    (net (code "56") (name "Net-(YDRIVER-A2)") (class "Default")
      (node (ref "YDRIVER") (pin "11") (pinfunction "A2_11") (pintype "bidirectional"))
      (node (ref "YOUT") (pin "8") (pinfunction "8_8") (pintype "passive"))
    )
    (net (code "57") (name "Net-(YDRIVER-B1)") (class "Default")
      (node (ref "YDRIVER") (pin "13") (pinfunction "B1_13") (pintype "bidirectional"))
      (node (ref "YOUT") (pin "4") (pinfunction "4_4") (pintype "passive"))
    )
    (net (code "58") (name "Net-(YDRIVER-B2)") (class "Default")
      (node (ref "YDRIVER") (pin "14") (pinfunction "B2_14") (pintype "bidirectional"))
      (node (ref "YOUT") (pin "7") (pinfunction "7_7") (pintype "passive"))
    )
    (net (code "59") (name "Net-(YDRIVER-FLT)") (class "Default")
      (node (ref "JP13") (pin "1") (pinfunction "1_1") (pintype "passive"))
      (node (ref "JP16") (pin "1") (pinfunction "1_1") (pintype "passive"))
      (node (ref "YDRIVER") (pin "10") (pinfunction "FLT_10") (pintype "bidirectional"))
    )
    (net (code "60") (name "Net-(YDRIVER-M0)") (class "Default")
      (node (ref "YDRIVER") (pin "2") (pinfunction "M0_2") (pintype "bidirectional"))
      (node (ref "YSET") (pin "5") (pinfunction "5_5") (pintype "passive"))
    )
    (net (code "61") (name "Net-(YDRIVER-M1)") (class "Default")
      (node (ref "YDRIVER") (pin "3") (pinfunction "M1_3") (pintype "bidirectional"))
      (node (ref "YSET") (pin "3") (pinfunction "3_3") (pintype "passive"))
    )
    (net (code "62") (name "Net-(YDRIVER-M2)") (class "Default")
      (node (ref "YDRIVER") (pin "4") (pinfunction "M2_4") (pintype "bidirectional"))
      (node (ref "YSET") (pin "1") (pinfunction "1_1") (pintype "passive"))
    )
    (net (code "63") (name "Net-(YDRIVER-STP)") (class "Default")
      (node (ref "JP6") (pin "1") (pinfunction "1_1") (pintype "passive"))
      (node (ref "YDRIVER") (pin "7") (pinfunction "STP_7") (pintype "bidirectional"))
      (node (ref "YSTP") (pin "4") (pinfunction "COL_4") (pintype "passive"))
      (node (ref "YSTP_UP") (pin "1") (pinfunction "1_1") (pintype "passive"))
    )
    (net (code "64") (name "Net-(YHOM-A)") (class "Default")
      (node (ref "YHOM") (pin "1") (pinfunction "A_1") (pintype "passive"))
      (node (ref "YHOME_IN") (pin "1") (pinfunction "1_1") (pintype "passive"))
    )
    (net (code "65") (name "Net-(YHOM-COL)") (class "Default")
      (node (ref "YHOM") (pin "4") (pinfunction "COL_4") (pintype "passive"))
      (node (ref "YHOME_OUT") (pin "1") (pinfunction "1_1") (pintype "passive"))
      (node (ref "YHOME_UP") (pin "1") (pinfunction "1_1") (pintype "passive"))
    )
    (net (code "66") (name "Net-(YHOME_IN-Pad2)") (class "Default")
      (node (ref "YHOME_IN") (pin "2") (pinfunction "2_2") (pintype "passive"))
      (node (ref "YOUT") (pin "1") (pinfunction "1_1") (pintype "passive"))
    )
    (net (code "67") (name "Net-(YSTP-A)") (class "Default")
      (node (ref "YSTP") (pin "1") (pinfunction "A_1") (pintype "passive"))
      (node (ref "YSTP_IN") (pin "1") (pinfunction "1_1") (pintype "passive"))
    )
    (net (code "68") (name "Net-(ZDIR-A)") (class "Default")
      (node (ref "ZDIR") (pin "1") (pinfunction "A_1") (pintype "passive"))
      (node (ref "ZDIR_IN") (pin "1") (pinfunction "1_1") (pintype "passive"))
    )
    (net (code "69") (name "Net-(ZDIR-COL)") (class "Default")
      (node (ref "JP7") (pin "1") (pinfunction "1_1") (pintype "passive"))
      (node (ref "ZDIR") (pin "4") (pinfunction "COL_4") (pintype "passive"))
      (node (ref "ZDIR_UP") (pin "1") (pinfunction "1_1") (pintype "passive"))
      (node (ref "ZDRIVER") (pin "8") (pinfunction "DIR_8") (pintype "bidirectional"))
    )
    (net (code "70") (name "Net-(ZDRIVER-A1)") (class "Default")
      (node (ref "ZDRIVER") (pin "12") (pinfunction "A1_12") (pintype "bidirectional"))
      (node (ref "ZOUT") (pin "5") (pinfunction "5_5") (pintype "passive"))
    )
    (net (code "71") (name "Net-(ZDRIVER-A2)") (class "Default")
      (node (ref "ZDRIVER") (pin "11") (pinfunction "A2_11") (pintype "bidirectional"))
      (node (ref "ZOUT") (pin "8") (pinfunction "8_8") (pintype "passive"))
    )
    (net (code "72") (name "Net-(ZDRIVER-B1)") (class "Default")
      (node (ref "ZDRIVER") (pin "13") (pinfunction "B1_13") (pintype "bidirectional"))
      (node (ref "ZOUT") (pin "4") (pinfunction "4_4") (pintype "passive"))
    )
    (net (code "73") (name "Net-(ZDRIVER-B2)") (class "Default")
      (node (ref "ZDRIVER") (pin "14") (pinfunction "B2_14") (pintype "bidirectional"))
      (node (ref "ZOUT") (pin "7") (pinfunction "7_7") (pintype "passive"))
    )
    (net (code "74") (name "Net-(ZDRIVER-FLT)") (class "Default")
      (node (ref "JP11") (pin "1") (pinfunction "1_1") (pintype "passive"))
      (node (ref "JP14") (pin "1") (pinfunction "1_1") (pintype "passive"))
      (node (ref "ZDRIVER") (pin "10") (pinfunction "FLT_10") (pintype "bidirectional"))
    )
    (net (code "75") (name "Net-(ZDRIVER-M0)") (class "Default")
      (node (ref "ZDRIVER") (pin "2") (pinfunction "M0_2") (pintype "bidirectional"))
      (node (ref "ZSET") (pin "5") (pinfunction "5_5") (pintype "passive"))
    )
    (net (code "76") (name "Net-(ZDRIVER-M1)") (class "Default")
      (node (ref "ZDRIVER") (pin "3") (pinfunction "M1_3") (pintype "bidirectional"))
      (node (ref "ZSET") (pin "3") (pinfunction "3_3") (pintype "passive"))
    )
    (net (code "77") (name "Net-(ZDRIVER-M2)") (class "Default")
      (node (ref "ZDRIVER") (pin "4") (pinfunction "M2_4") (pintype "bidirectional"))
      (node (ref "ZSET") (pin "1") (pinfunction "1_1") (pintype "passive"))
    )
    (net (code "78") (name "Net-(ZDRIVER-STP)") (class "Default")
      (node (ref "JP8") (pin "1") (pinfunction "1_1") (pintype "passive"))
      (node (ref "ZDRIVER") (pin "7") (pinfunction "STP_7") (pintype "bidirectional"))
      (node (ref "ZSTP") (pin "4") (pinfunction "COL_4") (pintype "passive"))
      (node (ref "ZSTP_UP") (pin "1") (pinfunction "1_1") (pintype "passive"))
    )
    (net (code "79") (name "Net-(ZHOM-A)") (class "Default")
      (node (ref "ZHOM") (pin "1") (pinfunction "A_1") (pintype "passive"))
      (node (ref "ZHOME_IN") (pin "1") (pinfunction "1_1") (pintype "passive"))
    )
    (net (code "80") (name "Net-(ZHOM-COL)") (class "Default")
      (node (ref "ZHOM") (pin "4") (pinfunction "COL_4") (pintype "passive"))
      (node (ref "ZHOME_OUT") (pin "1") (pinfunction "1_1") (pintype "passive"))
      (node (ref "ZHOME_UP") (pin "1") (pinfunction "1_1") (pintype "passive"))
    )
    (net (code "81") (name "Net-(ZHOME_IN-Pad2)") (class "Default")
      (node (ref "ZHOME_IN") (pin "2") (pinfunction "2_2") (pintype "passive"))
      (node (ref "ZOUT") (pin "1") (pinfunction "1_1") (pintype "passive"))
    )
    (net (code "82") (name "Net-(ZSTP-A)") (class "Default")
      (node (ref "ZSTP") (pin "1") (pinfunction "A_1") (pintype "passive"))
      (node (ref "ZSTP_IN") (pin "1") (pinfunction "1_1") (pintype "passive"))
    )
    (net (code "83") (name "V+") (class "Default")
      (node (ref "AC1") (pin "+") (pinfunction "+_+") (pintype "passive"))
      (node (ref "AC2") (pin "1") (pinfunction "1_1") (pintype "passive"))
      (node (ref "ADRIVER") (pin "16") (pinfunction "VMM_16") (pintype "bidirectional"))
      (node (ref "IC1") (pin "3") (pinfunction "VIN_3") (pintype "input"))
      (node (ref "RLED") (pin "2") (pinfunction "2_2") (pintype "passive"))
      (node (ref "X1") (pin "1") (pinfunction "KL_1") (pintype "passive"))
      (node (ref "XC1") (pin "+") (pinfunction "+_+") (pintype "passive"))
      (node (ref "XC2") (pin "1") (pinfunction "1_1") (pintype "passive"))
      (node (ref "XDRIVER") (pin "16") (pinfunction "VMM_16") (pintype "bidirectional"))
      (node (ref "YC1") (pin "+") (pinfunction "+_+") (pintype "passive"))
      (node (ref "YC2") (pin "1") (pinfunction "1_1") (pintype "passive"))
      (node (ref "YDRIVER") (pin "16") (pinfunction "VMM_16") (pintype "bidirectional"))
      (node (ref "ZC1") (pin "+") (pinfunction "+_+") (pintype "passive"))
      (node (ref "ZC2") (pin "1") (pinfunction "1_1") (pintype "passive"))
      (node (ref "ZDRIVER") (pin "16") (pinfunction "VMM_16") (pintype "bidirectional"))
    )
    (net (code "84") (name "VCC") (class "Default")
      (node (ref "AC3") (pin "1") (pinfunction "1_1") (pintype "passive"))
      (node (ref "ADIR_UP") (pin "2") (pinfunction "2_2") (pintype "passive"))
      (node (ref "ADRIVER") (pin "5") (pinfunction "RST_5") (pintype "bidirectional"))
      (node (ref "ADRIVER") (pin "6") (pinfunction "SLP_6") (pintype "bidirectional"))
      (node (ref "AHOME_UP") (pin "2") (pinfunction "2_2") (pintype "passive"))
      (node (ref "AOUT") (pin "6") (pinfunction "6_6") (pintype "passive"))
      (node (ref "ASET") (pin "2") (pinfunction "2_2") (pintype "passive"))
      (node (ref "ASET") (pin "4") (pinfunction "4_4") (pintype "passive"))
      (node (ref "ASET") (pin "6") (pinfunction "6_6") (pintype "passive"))
      (node (ref "ASTP_UP") (pin "2") (pinfunction "2_2") (pintype "passive"))
      (node (ref "EN_UP") (pin "2") (pinfunction "2_2") (pintype "passive"))
      (node (ref "FAULT_IN") (pin "2") (pinfunction "2_2") (pintype "passive"))
      (node (ref "FAULT_UP") (pin "2") (pinfunction "2_2") (pintype "passive"))
      (node (ref "IC1") (pin "2") (pinfunction "VOUT_2") (pintype "output"))
      (node (ref "RLED1") (pin "1") (pinfunction "1_1") (pintype "passive"))
      (node (ref "XC3") (pin "1") (pinfunction "1_1") (pintype "passive"))
      (node (ref "XDIR_UP") (pin "2") (pinfunction "2_2") (pintype "passive"))
      (node (ref "XDRIVER") (pin "5") (pinfunction "RST_5") (pintype "bidirectional"))
      (node (ref "XDRIVER") (pin "6") (pinfunction "SLP_6") (pintype "bidirectional"))
      (node (ref "XHOME_UP") (pin "2") (pinfunction "2_2") (pintype "passive"))
      (node (ref "XOUT") (pin "6") (pinfunction "6_6") (pintype "passive"))
      (node (ref "XSET") (pin "2") (pinfunction "2_2") (pintype "passive"))
      (node (ref "XSET") (pin "4") (pinfunction "4_4") (pintype "passive"))
      (node (ref "XSET") (pin "6") (pinfunction "6_6") (pintype "passive"))
      (node (ref "XSTP_UP") (pin "2") (pinfunction "2_2") (pintype "passive"))
      (node (ref "YC3") (pin "1") (pinfunction "1_1") (pintype "passive"))
      (node (ref "YDIR_UP") (pin "2") (pinfunction "2_2") (pintype "passive"))
      (node (ref "YDRIVER") (pin "5") (pinfunction "RST_5") (pintype "bidirectional"))
      (node (ref "YDRIVER") (pin "6") (pinfunction "SLP_6") (pintype "bidirectional"))
      (node (ref "YHOME_UP") (pin "2") (pinfunction "2_2") (pintype "passive"))
      (node (ref "YOUT") (pin "6") (pinfunction "6_6") (pintype "passive"))
      (node (ref "YSET") (pin "2") (pinfunction "2_2") (pintype "passive"))
      (node (ref "YSET") (pin "4") (pinfunction "4_4") (pintype "passive"))
      (node (ref "YSET") (pin "6") (pinfunction "6_6") (pintype "passive"))
      (node (ref "YSTP_UP") (pin "2") (pinfunction "2_2") (pintype "passive"))
      (node (ref "ZC3") (pin "1") (pinfunction "1_1") (pintype "passive"))
      (node (ref "ZDIR_UP") (pin "2") (pinfunction "2_2") (pintype "passive"))
      (node (ref "ZDRIVER") (pin "5") (pinfunction "RST_5") (pintype "bidirectional"))
      (node (ref "ZDRIVER") (pin "6") (pinfunction "SLP_6") (pintype "bidirectional"))
      (node (ref "ZHOME_UP") (pin "2") (pinfunction "2_2") (pintype "passive"))
      (node (ref "ZOUT") (pin "6") (pinfunction "6_6") (pintype "passive"))
      (node (ref "ZSET") (pin "2") (pinfunction "2_2") (pintype "passive"))
      (node (ref "ZSET") (pin "4") (pinfunction "4_4") (pintype "passive"))
      (node (ref "ZSET") (pin "6") (pinfunction "6_6") (pintype "passive"))
      (node (ref "ZSTP_UP") (pin "2") (pinfunction "2_2") (pintype "passive"))
    )
    (net (code "85") (name "unconnected-(DBF-F-Pad14)") (class "Default")
      (node (ref "DB") (pin "14") (pinfunction "F_14") (pintype "passive"))
    )
    (net (code "86") (name "unconnected-(DBH-F-Pad16)") (class "Default")
      (node (ref "DB") (pin "16") (pinfunction "F_16") (pintype "passive"))
    )
    (net (code "87") (name "unconnected-(DBI-F-Pad17)") (class "Default")
      (node (ref "DB") (pin "17") (pinfunction "F_17") (pintype "passive"))
    )
  )
)
